# controller-main.net
KiCad netlist of a schematic drawn in EAGLE
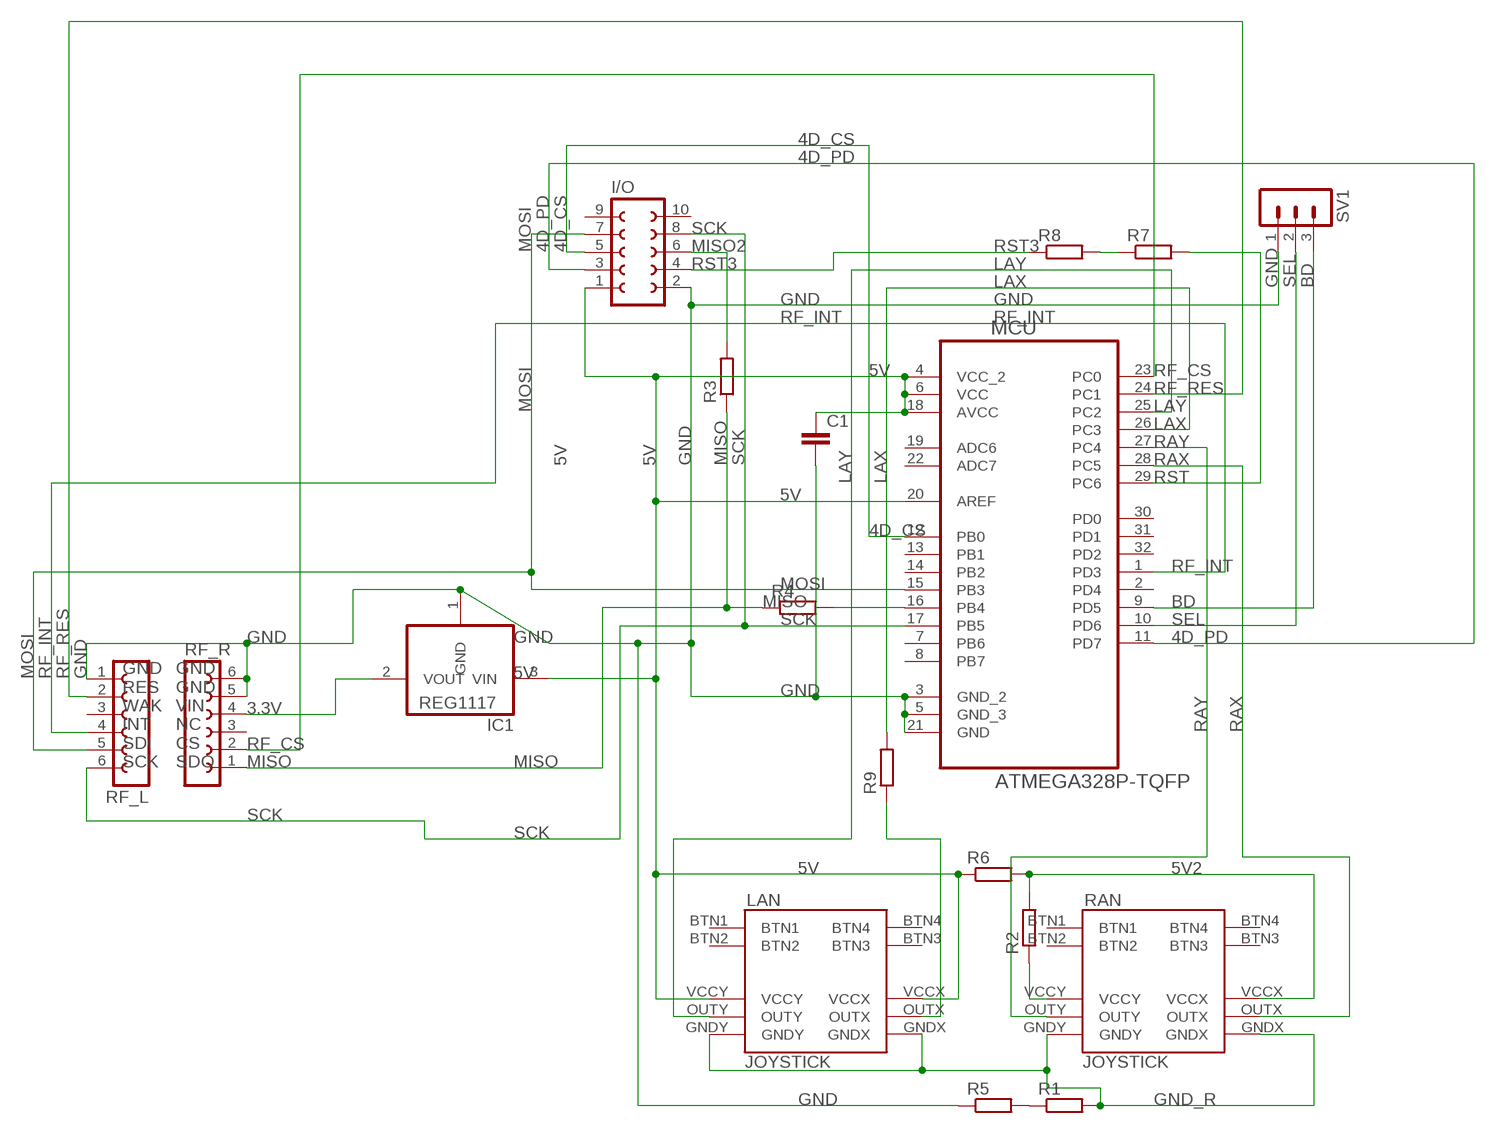
[diagram p0: schematic, sheet 1]

(export (version "E")
  (design (tool "Eeschema 10.0.6"))
  (components
    (comp (ref "C1")
      (value "C-EUC1206")
      (footprint "eagle-import:C1206")
      (libsource (lib "eagle-import") (part "C-EUC1206"))
    )
    (comp (ref "I/O")
      (value "FE05-2W")
      (footprint "eagle-import:FE05-2W")
      (libsource (lib "eagle-import") (part "FE05-2W"))
    )
    (comp (ref "IC1")
      (value "REG1117")
      (footprint "eagle-import:SOT223")
      (libsource (lib "eagle-import") (part "REG1117"))
    )
    (comp (ref "LAN")
      (value "JOYSTICK")
      (footprint "eagle-import:JOYSTICK")
      (libsource (lib "eagle-import") (part "JOYSTICKJOYSTICKWBTN"))
    )
    (comp (ref "MCU")
      (value "ATMEGA328P-TQFP")
      (footprint "eagle-import:QFP80P900X900X120-32N")
      (fields (field (name "MPN") "ATMEGA328P-AU"))
      (libsource (lib "eagle-import") (part "ATMEGA328P-AU"))
    )
    (comp (ref "R1")
      (value "R-EU_M1206")
      (footprint "eagle-import:M1206")
      (libsource (lib "eagle-import") (part "R-EU_M1206"))
    )
    (comp (ref "R2")
      (value "R-EU_M1206")
      (footprint "eagle-import:M1206")
      (libsource (lib "eagle-import") (part "R-EU_M1206"))
    )
    (comp (ref "R3")
      (value "R-EU_M1206")
      (footprint "eagle-import:M1206")
      (libsource (lib "eagle-import") (part "R-EU_M1206"))
    )
    (comp (ref "R4")
      (value "R-EU_M1206")
      (footprint "eagle-import:M1206")
      (libsource (lib "eagle-import") (part "R-EU_M1206"))
    )
    (comp (ref "R5")
      (value "R-EU_M1206")
      (footprint "eagle-import:M1206")
      (libsource (lib "eagle-import") (part "R-EU_M1206"))
    )
    (comp (ref "R6")
      (value "R-EU_M1206")
      (footprint "eagle-import:M1206")
      (libsource (lib "eagle-import") (part "R-EU_M1206"))
    )
    (comp (ref "R7")
      (value "R-EU_M1206")
      (footprint "eagle-import:M1206")
      (libsource (lib "eagle-import") (part "R-EU_M1206"))
    )
    (comp (ref "R8")
      (value "R-EU_M1206")
      (footprint "eagle-import:M1206")
      (libsource (lib "eagle-import") (part "R-EU_M1206"))
    )
    (comp (ref "R9")
      (value "R-EU_M1206")
      (footprint "eagle-import:M1206")
      (libsource (lib "eagle-import") (part "R-EU_M1206"))
    )
    (comp (ref "RAN")
      (value "JOYSTICK")
      (footprint "eagle-import:JOYSTICK")
      (libsource (lib "eagle-import") (part "JOYSTICKJOYSTICKWBTN"))
    )
    (comp (ref "RF_L")
      (value "FE06-1")
      (footprint "eagle-import:FE06")
      (libsource (lib "eagle-import") (part "FE06-1"))
    )
    (comp (ref "RF_R")
      (value "FE06-1")
      (footprint "eagle-import:FE06")
      (libsource (lib "eagle-import") (part "FE06-1"))
    )
    (comp (ref "SV1")
      (value "MA03-1")
      (footprint "eagle-import:MA03-1")
      (libsource (lib "eagle-import") (part "MA03-1"))
    )
  )
  (nets
    (net (code "1") (name "/3.3V") (class "Default")
      (node (ref "IC1") (pin "2") (pinfunction "VOUT_2") (pintype "output"))
      (node (ref "RF_R") (pin "4") (pinfunction "4_4") (pintype "passive"))
    )
    (net (code "2") (name "/4D_CS") (class "Default")
      (node (ref "I/O") (pin "5") (pinfunction "5_5") (pintype "passive"))
      (node (ref "MCU") (pin "12") (pinfunction "PB0_12") (pintype "bidirectional"))
    )
    (net (code "3") (name "/4D_PD") (class "Default")
      (node (ref "I/O") (pin "3") (pinfunction "3_3") (pintype "passive"))
      (node (ref "MCU") (pin "11") (pinfunction "PD7_11") (pintype "bidirectional"))
    )
    (net (code "4") (name "/5V") (class "Default")
      (node (ref "C1") (pin "1") (pinfunction "1_1") (pintype "passive"))
      (node (ref "I/O") (pin "1") (pinfunction "1_1") (pintype "passive"))
      (node (ref "IC1") (pin "3") (pinfunction "VIN_3") (pintype "input"))
      (node (ref "LAN") (pin "VCCX") (pinfunction "VCCX_VCCX") (pintype "bidirectional"))
      (node (ref "LAN") (pin "VCCY") (pinfunction "VCCY_VCCY") (pintype "bidirectional"))
      (node (ref "MCU") (pin "18") (pinfunction "AVCC_18") (pintype "power_in"))
      (node (ref "MCU") (pin "20") (pinfunction "AREF_20") (pintype "input"))
      (node (ref "MCU") (pin "4") (pinfunction "VCC_2_4") (pintype "power_in"))
      (node (ref "MCU") (pin "6") (pinfunction "VCC_6") (pintype "power_in"))
      (node (ref "R6") (pin "1") (pinfunction "1_1") (pintype "passive"))
    )
    (net (code "5") (name "/5V2") (class "Default")
      (node (ref "R2") (pin "2") (pinfunction "2_2") (pintype "passive"))
      (node (ref "R6") (pin "2") (pinfunction "2_2") (pintype "passive"))
      (node (ref "RAN") (pin "VCCX") (pinfunction "VCCX_VCCX") (pintype "bidirectional"))
    )
    (net (code "6") (name "/BD") (class "Default")
      (node (ref "MCU") (pin "9") (pinfunction "PD5_9") (pintype "bidirectional"))
      (node (ref "SV1") (pin "3") (pinfunction "3_3") (pintype "passive"))
    )
    (net (code "7") (name "/GND") (class "Default")
      (node (ref "C1") (pin "2") (pinfunction "2_2") (pintype "passive"))
      (node (ref "I/O") (pin "2") (pinfunction "2_2") (pintype "passive"))
      (node (ref "IC1") (pin "1") (pinfunction "GND_1") (pintype "power_in"))
      (node (ref "MCU") (pin "21") (pinfunction "GND_21") (pintype "passive"))
      (node (ref "MCU") (pin "3") (pinfunction "GND_2_3") (pintype "passive"))
      (node (ref "MCU") (pin "5") (pinfunction "GND_3_5") (pintype "passive"))
      (node (ref "R5") (pin "1") (pinfunction "1_1") (pintype "passive"))
      (node (ref "RF_L") (pin "1") (pinfunction "1_1") (pintype "passive"))
      (node (ref "RF_R") (pin "5") (pinfunction "5_5") (pintype "passive"))
      (node (ref "RF_R") (pin "6") (pinfunction "6_6") (pintype "passive"))
      (node (ref "SV1") (pin "1") (pinfunction "1_1") (pintype "passive"))
    )
    (net (code "8") (name "/GND_R") (class "Default")
      (node (ref "LAN") (pin "GNDX") (pinfunction "GNDX_GNDX") (pintype "bidirectional"))
      (node (ref "LAN") (pin "GNDY") (pinfunction "GNDY_GNDY") (pintype "bidirectional"))
      (node (ref "R1") (pin "2") (pinfunction "2_2") (pintype "passive"))
      (node (ref "RAN") (pin "GNDX") (pinfunction "GNDX_GNDX") (pintype "bidirectional"))
      (node (ref "RAN") (pin "GNDY") (pinfunction "GNDY_GNDY") (pintype "bidirectional"))
    )
    (net (code "9") (name "/LAX") (class "Default")
      (node (ref "MCU") (pin "26") (pinfunction "PC3_26") (pintype "bidirectional"))
      (node (ref "R9") (pin "2") (pinfunction "2_2") (pintype "passive"))
    )
    (net (code "10") (name "/LAY") (class "Default")
      (node (ref "LAN") (pin "OUTY") (pinfunction "OUTY_OUTY") (pintype "bidirectional"))
      (node (ref "MCU") (pin "25") (pinfunction "PC2_25") (pintype "bidirectional"))
    )
    (net (code "11") (name "/MISO") (class "Default")
      (node (ref "R3") (pin "1") (pinfunction "1_1") (pintype "passive"))
      (node (ref "R4") (pin "1") (pinfunction "1_1") (pintype "passive"))
      (node (ref "RF_R") (pin "1") (pinfunction "1_1") (pintype "passive"))
    )
    (net (code "12") (name "/MISO2") (class "Default")
      (node (ref "I/O") (pin "6") (pinfunction "6_6") (pintype "passive"))
      (node (ref "R3") (pin "2") (pinfunction "2_2") (pintype "passive"))
    )
    (net (code "13") (name "/MOSI") (class "Default")
      (node (ref "I/O") (pin "7") (pinfunction "7_7") (pintype "passive"))
      (node (ref "MCU") (pin "15") (pinfunction "PB3_15") (pintype "bidirectional"))
      (node (ref "RF_L") (pin "5") (pinfunction "5_5") (pintype "passive"))
    )
    (net (code "14") (name "/RAX") (class "Default")
      (node (ref "MCU") (pin "28") (pinfunction "PC5_28") (pintype "bidirectional"))
      (node (ref "RAN") (pin "OUTX") (pinfunction "OUTX_OUTX") (pintype "bidirectional"))
    )
    (net (code "15") (name "/RAY") (class "Default")
      (node (ref "MCU") (pin "27") (pinfunction "PC4_27") (pintype "bidirectional"))
      (node (ref "RAN") (pin "OUTY") (pinfunction "OUTY_OUTY") (pintype "bidirectional"))
    )
    (net (code "16") (name "/RF_CS") (class "Default")
      (node (ref "MCU") (pin "23") (pinfunction "PC0_23") (pintype "bidirectional"))
      (node (ref "RF_R") (pin "2") (pinfunction "2_2") (pintype "passive"))
    )
    (net (code "17") (name "/RF_INT") (class "Default")
      (node (ref "MCU") (pin "1") (pinfunction "PD3_1") (pintype "bidirectional"))
      (node (ref "RF_L") (pin "4") (pinfunction "4_4") (pintype "passive"))
    )
    (net (code "18") (name "/RF_RES") (class "Default")
      (node (ref "MCU") (pin "24") (pinfunction "PC1_24") (pintype "bidirectional"))
      (node (ref "RF_L") (pin "2") (pinfunction "2_2") (pintype "passive"))
    )
    (net (code "19") (name "/RST") (class "Default")
      (node (ref "MCU") (pin "29") (pinfunction "PC6_29") (pintype "bidirectional"))
      (node (ref "R7") (pin "2") (pinfunction "2_2") (pintype "passive"))
    )
    (net (code "20") (name "/RST3") (class "Default")
      (node (ref "I/O") (pin "4") (pinfunction "4_4") (pintype "passive"))
      (node (ref "R8") (pin "1") (pinfunction "1_1") (pintype "passive"))
    )
    (net (code "21") (name "/SCK") (class "Default")
      (node (ref "I/O") (pin "8") (pinfunction "8_8") (pintype "passive"))
      (node (ref "MCU") (pin "17") (pinfunction "PB5_17") (pintype "bidirectional"))
      (node (ref "RF_L") (pin "6") (pinfunction "6_6") (pintype "passive"))
    )
    (net (code "22") (name "/SEL") (class "Default")
      (node (ref "MCU") (pin "10") (pinfunction "PD6_10") (pintype "bidirectional"))
      (node (ref "SV1") (pin "2") (pinfunction "2_2") (pintype "passive"))
    )
    (net (code "23") (name "Net-(LAN-PadOUTX)") (class "Default")
      (node (ref "LAN") (pin "OUTX") (pinfunction "OUTX_OUTX") (pintype "bidirectional"))
      (node (ref "R9") (pin "1") (pinfunction "1_1") (pintype "passive"))
    )
    (net (code "24") (name "Net-(MCU-PB4)") (class "Default")
      (node (ref "MCU") (pin "16") (pinfunction "PB4_16") (pintype "bidirectional"))
      (node (ref "R4") (pin "2") (pinfunction "2_2") (pintype "passive"))
    )
    (net (code "25") (name "Net-(R1-Pad1)") (class "Default")
      (node (ref "R1") (pin "1") (pinfunction "1_1") (pintype "passive"))
      (node (ref "R5") (pin "2") (pinfunction "2_2") (pintype "passive"))
    )
    (net (code "26") (name "Net-(R2-Pad1)") (class "Default")
      (node (ref "R2") (pin "1") (pinfunction "1_1") (pintype "passive"))
      (node (ref "RAN") (pin "VCCY") (pinfunction "VCCY_VCCY") (pintype "bidirectional"))
    )
    (net (code "27") (name "Net-(R7-Pad1)") (class "Default")
      (node (ref "R7") (pin "1") (pinfunction "1_1") (pintype "passive"))
      (node (ref "R8") (pin "2") (pinfunction "2_2") (pintype "passive"))
    )
    (net (code "28") (name "unconnected-(I/O-Pad9)") (class "Default")
      (node (ref "I/O") (pin "9") (pinfunction "9_9") (pintype "passive"))
    )
    (net (code "29") (name "unconnected-(I/O-Pad10)") (class "Default")
      (node (ref "I/O") (pin "10") (pinfunction "10_10") (pintype "passive"))
    )
    (net (code "30") (name "unconnected-(LAN-PadBTN1)") (class "Default")
      (node (ref "LAN") (pin "BTN1") (pinfunction "BTN1_BTN1") (pintype "bidirectional"))
    )
    (net (code "31") (name "unconnected-(LAN-PadBTN2)") (class "Default")
      (node (ref "LAN") (pin "BTN2") (pinfunction "BTN2_BTN2") (pintype "bidirectional"))
    )
    (net (code "32") (name "unconnected-(LAN-PadBTN3)") (class "Default")
      (node (ref "LAN") (pin "BTN3") (pinfunction "BTN3_BTN3") (pintype "bidirectional"))
    )
    (net (code "33") (name "unconnected-(LAN-PadBTN4)") (class "Default")
      (node (ref "LAN") (pin "BTN4") (pinfunction "BTN4_BTN4") (pintype "bidirectional"))
    )
    (net (code "34") (name "unconnected-(MCU-ADC6-Pad19)") (class "Default")
      (node (ref "MCU") (pin "19") (pinfunction "ADC6_19") (pintype "input"))
    )
    (net (code "35") (name "unconnected-(MCU-ADC7-Pad22)") (class "Default")
      (node (ref "MCU") (pin "22") (pinfunction "ADC7_22") (pintype "input"))
    )
    (net (code "36") (name "unconnected-(MCU-PB1-Pad13)") (class "Default")
      (node (ref "MCU") (pin "13") (pinfunction "PB1_13") (pintype "bidirectional"))
    )
    (net (code "37") (name "unconnected-(MCU-PB2-Pad14)") (class "Default")
      (node (ref "MCU") (pin "14") (pinfunction "PB2_14") (pintype "bidirectional"))
    )
    (net (code "38") (name "unconnected-(MCU-PB6-Pad7)") (class "Default")
      (node (ref "MCU") (pin "7") (pinfunction "PB6_7") (pintype "bidirectional"))
    )
    (net (code "39") (name "unconnected-(MCU-PB7-Pad8)") (class "Default")
      (node (ref "MCU") (pin "8") (pinfunction "PB7_8") (pintype "bidirectional"))
    )
    (net (code "40") (name "unconnected-(MCU-PD0-Pad30)") (class "Default")
      (node (ref "MCU") (pin "30") (pinfunction "PD0_30") (pintype "bidirectional"))
    )
    (net (code "41") (name "unconnected-(MCU-PD1-Pad31)") (class "Default")
      (node (ref "MCU") (pin "31") (pinfunction "PD1_31") (pintype "bidirectional"))
    )
    (net (code "42") (name "unconnected-(MCU-PD2-Pad32)") (class "Default")
      (node (ref "MCU") (pin "32") (pinfunction "PD2_32") (pintype "bidirectional"))
    )
    (net (code "43") (name "unconnected-(MCU-PD4-Pad2)") (class "Default")
      (node (ref "MCU") (pin "2") (pinfunction "PD4_2") (pintype "bidirectional"))
    )
    (net (code "44") (name "unconnected-(RAN-PadBTN1)") (class "Default")
      (node (ref "RAN") (pin "BTN1") (pinfunction "BTN1_BTN1") (pintype "bidirectional"))
    )
    (net (code "45") (name "unconnected-(RAN-PadBTN2)") (class "Default")
      (node (ref "RAN") (pin "BTN2") (pinfunction "BTN2_BTN2") (pintype "bidirectional"))
    )
    (net (code "46") (name "unconnected-(RAN-PadBTN3)") (class "Default")
      (node (ref "RAN") (pin "BTN3") (pinfunction "BTN3_BTN3") (pintype "bidirectional"))
    )
    (net (code "47") (name "unconnected-(RAN-PadBTN4)") (class "Default")
      (node (ref "RAN") (pin "BTN4") (pinfunction "BTN4_BTN4") (pintype "bidirectional"))
    )
    (net (code "48") (name "unconnected-(RF_L-Pad3)") (class "Default")
      (node (ref "RF_L") (pin "3") (pinfunction "3_3") (pintype "passive"))
    )
    (net (code "49") (name "unconnected-(RF_R-Pad3)") (class "Default")
      (node (ref "RF_R") (pin "3") (pinfunction "3_3") (pintype "passive"))
    )
  )
)
